# led-bike-suit-vest.net
KiCad netlist of a schematic drawn in EAGLE
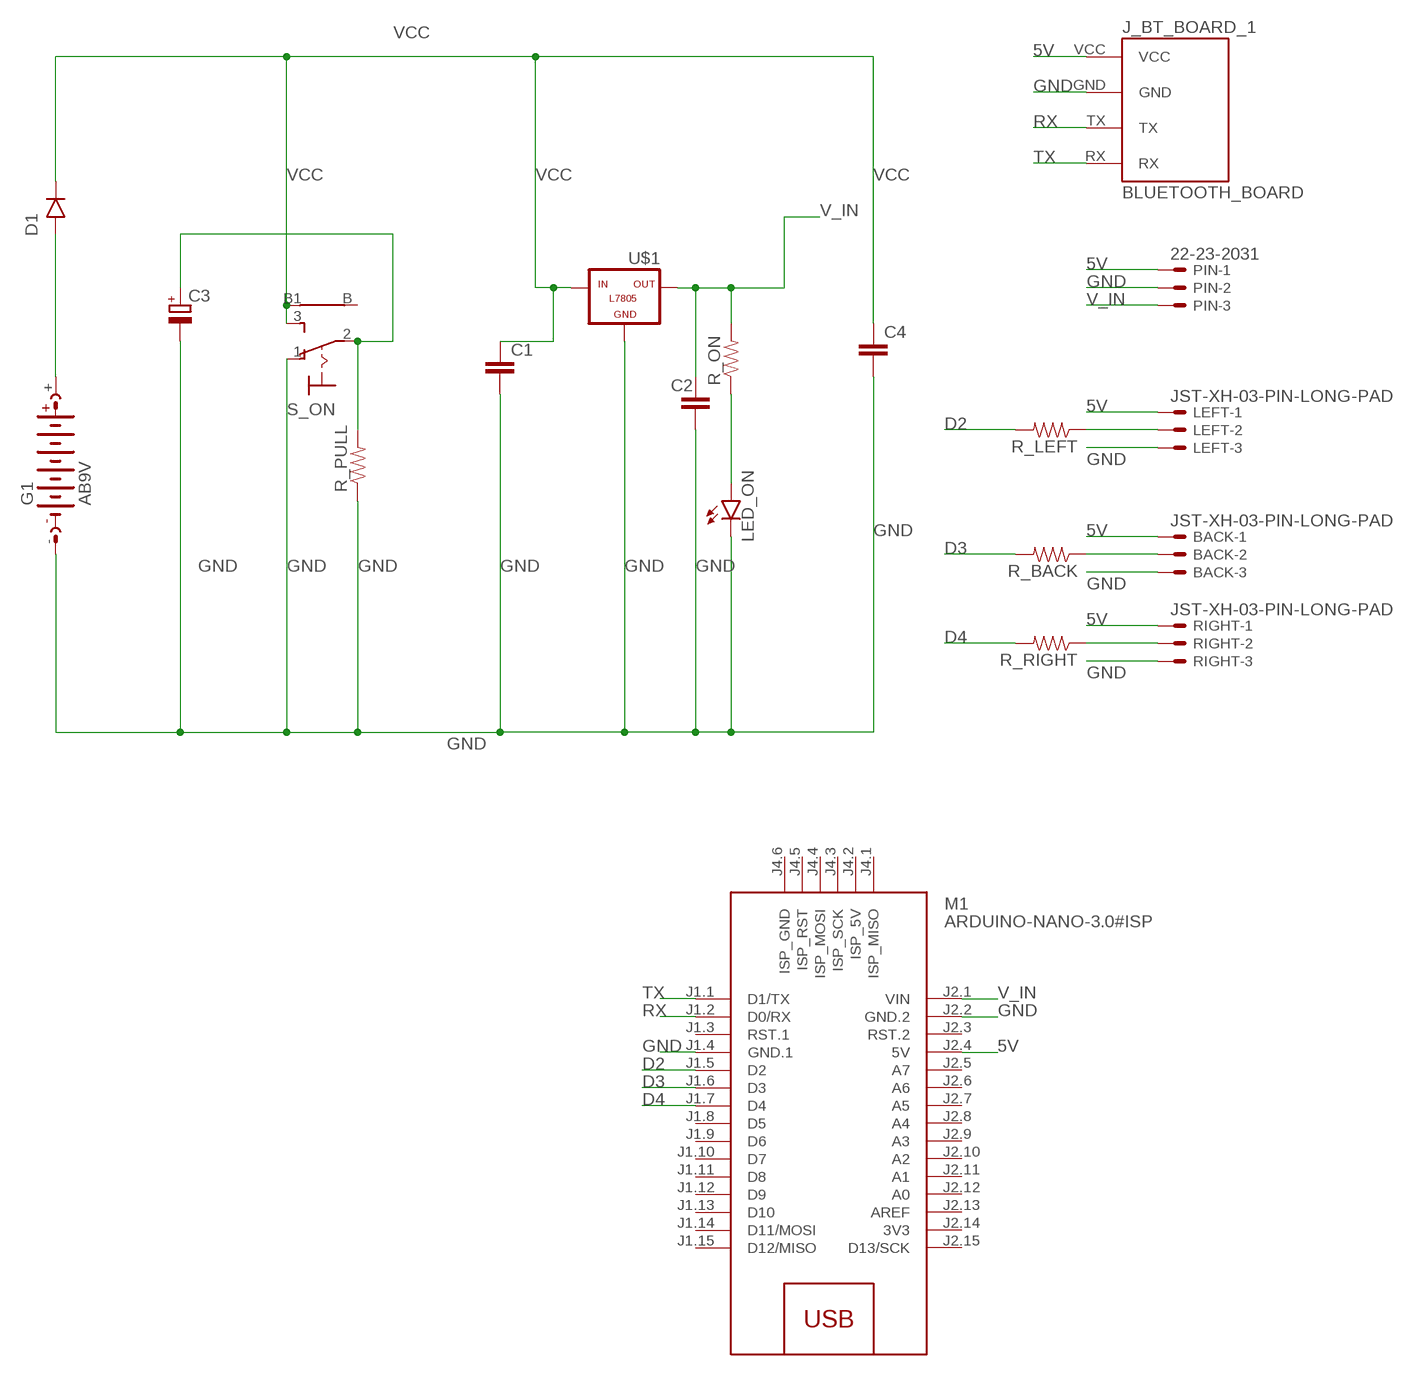
[diagram p0: schematic, sheet 1]

(export (version "E")
  (design (tool "Eeschema 10.0.6"))
  (components
    (comp (ref "BACK")
      (value "JST-XH-03-PIN-LONG-PAD")
      (footprint "eagle-import:JST-XH-03-PACKAGE-LONG-PAD")
      (libsource (lib "eagle-import") (part "JST-XH-03-PIN-LONG-PAD"))
    )
    (comp (ref "C1")
      (value "C2.5/4")
      (footprint "eagle-import:C2.5-4")
      (libsource (lib "eagle-import") (part "C2.5/4"))
    )
    (comp (ref "C2")
      (value "C2.5/4")
      (footprint "eagle-import:C2.5-4")
      (libsource (lib "eagle-import") (part "C2.5/4"))
    )
    (comp (ref "C3")
      (value "RCL_CPOL-EUE3.5-8")
      (footprint "eagle-import:ELECTROLYTIC_CAP_RCL_E3,5-8")
      (libsource (lib "eagle-import") (part "RCL_CPOL-EUE3.5-8"))
    )
    (comp (ref "C4")
      (value "C2.5/4")
      (footprint "eagle-import:C2.5-4")
      (libsource (lib "eagle-import") (part "C2.5/4"))
    )
    (comp (ref "D1")
      (value "1N4001")
      (footprint "eagle-import:DO41-10")
      (libsource (lib "eagle-import") (part "1N4001"))
    )
    (comp (ref "G1")
      (value "AB9V")
      (footprint "eagle-import:AB9V")
      (libsource (lib "eagle-import") (part "AB9V"))
    )
    (comp (ref "J_BT_BOARD_1")
      (value "BLUETOOTH_BOARD")
      (footprint "eagle-import:BT_BOARD_FOOTPRINT")
      (libsource (lib "eagle-import") (part "BLUETOOTH_BOARD"))
    )
    (comp (ref "LED_ON")
      (value "LED5MM")
      (footprint "eagle-import:LED5MM")
      (libsource (lib "eagle-import") (part "LED5MM"))
    )
    (comp (ref "LEFT")
      (value "JST-XH-03-PIN-LONG-PAD")
      (footprint "eagle-import:JST-XH-03-PACKAGE-LONG-PAD")
      (libsource (lib "eagle-import") (part "JST-XH-03-PIN-LONG-PAD"))
    )
    (comp (ref "M1")
      (value "ARDUINO-NANO-3.0#ISP")
      (footprint "eagle-import:ARDUINO-NANO-3.0#ISP")
      (libsource (lib "eagle-import") (part "ARDUINO-NANO-3.0#ISP"))
    )
    (comp (ref "PIN")
      (value "22-23-2031")
      (footprint "eagle-import:22-23-2031")
      (fields (field (name "MF") "MOLEX"))
      (libsource (lib "eagle-import") (part "22-23-2031"))
    )
    (comp (ref "RIGHT")
      (value "JST-XH-03-PIN-LONG-PAD")
      (footprint "eagle-import:JST-XH-03-PACKAGE-LONG-PAD")
      (libsource (lib "eagle-import") (part "JST-XH-03-PIN-LONG-PAD"))
    )
    (comp (ref "R_BACK")
      (value "PASSIVES_RESISTORPTH-1/4W")
      (footprint "eagle-import:SPARKFUN-PASSIVES_AXIAL-0.4")
      (libsource (lib "eagle-import") (part "PASSIVES_RESISTORPTH-1/4W"))
    )
    (comp (ref "R_LEFT")
      (value "PASSIVES_RESISTORPTH-1/4W")
      (footprint "eagle-import:SPARKFUN-PASSIVES_AXIAL-0.4")
      (libsource (lib "eagle-import") (part "PASSIVES_RESISTORPTH-1/4W"))
    )
    (comp (ref "R_ON")
      (value "PASSIVES_RESISTORPTH-1/4W")
      (footprint "eagle-import:SPARKFUN-PASSIVES_AXIAL-0.4")
      (libsource (lib "eagle-import") (part "PASSIVES_RESISTORPTH-1/4W"))
    )
    (comp (ref "R_PULL")
      (value "PASSIVES_RESISTORPTH-1/4W")
      (footprint "eagle-import:SPARKFUN-PASSIVES_AXIAL-0.4")
      (libsource (lib "eagle-import") (part "PASSIVES_RESISTORPTH-1/4W"))
    )
    (comp (ref "R_RIGHT")
      (value "PASSIVES_RESISTORPTH-1/4W")
      (footprint "eagle-import:SPARKFUN-PASSIVES_AXIAL-0.4")
      (libsource (lib "eagle-import") (part "PASSIVES_RESISTORPTH-1/4W"))
    )
    (comp (ref "S_ON")
      (value "9070-1W")
      (footprint "eagle-import:9070-1W")
      (libsource (lib "eagle-import") (part "9070-1W"))
    )
    (comp (ref "U$1")
      (value "-L7805")
      (footprint "eagle-import:L7805")
      (libsource (lib "eagle-import") (part "-L7805"))
    )
  )
  (nets
    (net (code "1") (name "/3V3") (class "Default")
      (node (ref "M1") (pin "J2.14") (pinfunction "3V3_J2.14") (pintype "power_in"))
    )
    (net (code "2") (name "/5V") (class "Default")
      (node (ref "BACK") (pin "1") (pinfunction "S_1") (pintype "passive"))
      (node (ref "J_BT_BOARD_1") (pin "VCC") (pinfunction "VCC_VCC") (pintype "bidirectional"))
      (node (ref "LEFT") (pin "1") (pinfunction "S_1") (pintype "passive"))
      (node (ref "M1") (pin "J2.4") (pinfunction "5V_J2.4") (pintype "power_in"))
      (node (ref "PIN") (pin "1") (pinfunction "S_1") (pintype "passive"))
      (node (ref "RIGHT") (pin "1") (pinfunction "S_1") (pintype "passive"))
    )
    (net (code "3") (name "/D2") (class "Default")
      (node (ref "M1") (pin "J1.5") (pinfunction "D2_J1.5") (pintype "bidirectional"))
      (node (ref "R_LEFT") (pin "P$2") (pinfunction "2_P$2") (pintype "passive"))
    )
    (net (code "4") (name "/D3") (class "Default")
      (node (ref "M1") (pin "J1.6") (pinfunction "D3_J1.6") (pintype "bidirectional"))
      (node (ref "R_BACK") (pin "P$2") (pinfunction "2_P$2") (pintype "passive"))
    )
    (net (code "5") (name "/D4") (class "Default")
      (node (ref "M1") (pin "J1.7") (pinfunction "D4_J1.7") (pintype "bidirectional"))
      (node (ref "R_RIGHT") (pin "P$2") (pinfunction "2_P$2") (pintype "passive"))
    )
    (net (code "6") (name "/GND") (class "Default")
      (node (ref "BACK") (pin "3") (pinfunction "S_3") (pintype "passive"))
      (node (ref "C1") (pin "2") (pinfunction "2_2") (pintype "passive"))
      (node (ref "C2") (pin "2") (pinfunction "2_2") (pintype "passive"))
      (node (ref "C3") (pin "-") (pinfunction "-_-") (pintype "passive"))
      (node (ref "C4") (pin "2") (pinfunction "2_2") (pintype "passive"))
      (node (ref "G1") (pin "-") (pinfunction "-_-") (pintype "passive"))
      (node (ref "J_BT_BOARD_1") (pin "GND") (pinfunction "GND_GND") (pintype "bidirectional"))
      (node (ref "LED_ON") (pin "K") (pinfunction "CATHODE_K") (pintype "passive"))
      (node (ref "LEFT") (pin "3") (pinfunction "S_3") (pintype "passive"))
      (node (ref "M1") (pin "J1.4") (pinfunction "GND.1_J1.4") (pintype "power_in"))
      (node (ref "M1") (pin "J2.2") (pinfunction "GND.2_J2.2") (pintype "power_in"))
      (node (ref "PIN") (pin "2") (pinfunction "S_2") (pintype "passive"))
      (node (ref "RIGHT") (pin "3") (pinfunction "S_3") (pintype "passive"))
      (node (ref "R_PULL") (pin "P$1") (pinfunction "1_P$1") (pintype "passive"))
      (node (ref "S_ON") (pin "1") (pinfunction "O_1") (pintype "passive"))
      (node (ref "U$1") (pin "GND") (pinfunction "GND_GND") (pintype "input"))
    )
    (net (code "7") (name "/RX") (class "Default")
      (node (ref "J_BT_BOARD_1") (pin "TX") (pinfunction "TX_TX") (pintype "bidirectional"))
      (node (ref "M1") (pin "J1.2") (pinfunction "D0/RX_J1.2") (pintype "bidirectional"))
    )
    (net (code "8") (name "/TX") (class "Default")
      (node (ref "J_BT_BOARD_1") (pin "RX") (pinfunction "RX_RX") (pintype "bidirectional"))
      (node (ref "M1") (pin "J1.1") (pinfunction "D1/TX_J1.1") (pintype "bidirectional"))
    )
    (net (code "9") (name "/VCC") (class "Default")
      (node (ref "C1") (pin "1") (pinfunction "1_1") (pintype "passive"))
      (node (ref "C4") (pin "1") (pinfunction "1_1") (pintype "passive"))
      (node (ref "D1") (pin "C") (pinfunction "CATHODE_C") (pintype "passive"))
      (node (ref "S_ON") (pin "3") (pinfunction "S_3") (pintype "passive"))
      (node (ref "S_ON") (pin "B1") (pinfunction "B1_B1") (pintype "passive"))
      (node (ref "U$1") (pin "IN") (pinfunction "IN_IN") (pintype "input"))
    )
    (net (code "10") (name "/V_IN") (class "Default")
      (node (ref "C2") (pin "1") (pinfunction "1_1") (pintype "passive"))
      (node (ref "M1") (pin "J2.1") (pinfunction "VIN_J2.1") (pintype "power_in"))
      (node (ref "PIN") (pin "3") (pinfunction "S_3") (pintype "passive"))
      (node (ref "R_ON") (pin "P$2") (pinfunction "2_P$2") (pintype "passive"))
      (node (ref "U$1") (pin "OUT") (pinfunction "OUT_OUT") (pintype "passive"))
    )
    (net (code "11") (name "Net-(BACKB-S)") (class "Default")
      (node (ref "BACK") (pin "2") (pinfunction "S_2") (pintype "passive"))
      (node (ref "R_BACK") (pin "P$1") (pinfunction "1_P$1") (pintype "passive"))
    )
    (net (code "12") (name "Net-(D1-ANODE)") (class "Default")
      (node (ref "D1") (pin "A") (pinfunction "ANODE_A") (pintype "passive"))
      (node (ref "G1") (pin "+") (pinfunction "+_+") (pintype "passive"))
    )
    (net (code "13") (name "Net-(LED_ON-ANODE)") (class "Default")
      (node (ref "LED_ON") (pin "A") (pinfunction "ANODE_A") (pintype "passive"))
      (node (ref "R_ON") (pin "P$1") (pinfunction "1_P$1") (pintype "passive"))
    )
    (net (code "14") (name "Net-(LEFTB-S)") (class "Default")
      (node (ref "LEFT") (pin "2") (pinfunction "S_2") (pintype "passive"))
      (node (ref "R_LEFT") (pin "P$1") (pinfunction "1_P$1") (pintype "passive"))
    )
    (net (code "15") (name "Net-(RIGHTB-S)") (class "Default")
      (node (ref "RIGHT") (pin "2") (pinfunction "S_2") (pintype "passive"))
      (node (ref "R_RIGHT") (pin "P$1") (pinfunction "1_P$1") (pintype "passive"))
    )
    (net (code "16") (name "Net-(R_PULL-2)") (class "Default")
      (node (ref "C3") (pin "+") (pinfunction "+_+") (pintype "passive"))
      (node (ref "R_PULL") (pin "P$2") (pinfunction "2_P$2") (pintype "passive"))
      (node (ref "S_ON") (pin "2") (pinfunction "P_2") (pintype "passive"))
    )
    (net (code "17") (name "unconnected-(M1-A0-PadJ2.12)") (class "Default")
      (node (ref "M1") (pin "J2.12") (pinfunction "A0_J2.12") (pintype "bidirectional"))
    )
    (net (code "18") (name "unconnected-(M1-A1-PadJ2.11)") (class "Default")
      (node (ref "M1") (pin "J2.11") (pinfunction "A1_J2.11") (pintype "bidirectional"))
    )
    (net (code "19") (name "unconnected-(M1-A2-PadJ2.10)") (class "Default")
      (node (ref "M1") (pin "J2.10") (pinfunction "A2_J2.10") (pintype "bidirectional"))
    )
    (net (code "20") (name "unconnected-(M1-A3-PadJ2.9)") (class "Default")
      (node (ref "M1") (pin "J2.9") (pinfunction "A3_J2.9") (pintype "bidirectional"))
    )
    (net (code "21") (name "unconnected-(M1-A4-PadJ2.8)") (class "Default")
      (node (ref "M1") (pin "J2.8") (pinfunction "A4_J2.8") (pintype "bidirectional"))
    )
    (net (code "22") (name "unconnected-(M1-A5-PadJ2.7)") (class "Default")
      (node (ref "M1") (pin "J2.7") (pinfunction "A5_J2.7") (pintype "bidirectional"))
    )
    (net (code "23") (name "unconnected-(M1-A6-PadJ2.6)") (class "Default")
      (node (ref "M1") (pin "J2.6") (pinfunction "A6_J2.6") (pintype "bidirectional"))
    )
    (net (code "24") (name "unconnected-(M1-A7-PadJ2.5)") (class "Default")
      (node (ref "M1") (pin "J2.5") (pinfunction "A7_J2.5") (pintype "bidirectional"))
    )
    (net (code "25") (name "unconnected-(M1-AREF-PadJ2.13)") (class "Default")
      (node (ref "M1") (pin "J2.13") (pinfunction "AREF_J2.13") (pintype "bidirectional"))
    )
    (net (code "26") (name "unconnected-(M1-D5-PadJ1.8)") (class "Default")
      (node (ref "M1") (pin "J1.8") (pinfunction "D5_J1.8") (pintype "bidirectional"))
    )
    (net (code "27") (name "unconnected-(M1-D6-PadJ1.9)") (class "Default")
      (node (ref "M1") (pin "J1.9") (pinfunction "D6_J1.9") (pintype "bidirectional"))
    )
    (net (code "28") (name "unconnected-(M1-D7-PadJ1.10)") (class "Default")
      (node (ref "M1") (pin "J1.10") (pinfunction "D7_J1.10") (pintype "bidirectional"))
    )
    (net (code "29") (name "unconnected-(M1-D8-PadJ1.11)") (class "Default")
      (node (ref "M1") (pin "J1.11") (pinfunction "D8_J1.11") (pintype "bidirectional"))
    )
    (net (code "30") (name "unconnected-(M1-D9-PadJ1.12)") (class "Default")
      (node (ref "M1") (pin "J1.12") (pinfunction "D9_J1.12") (pintype "bidirectional"))
    )
    (net (code "31") (name "unconnected-(M1-D10-PadJ1.13)") (class "Default")
      (node (ref "M1") (pin "J1.13") (pinfunction "D10_J1.13") (pintype "bidirectional"))
    )
    (net (code "32") (name "unconnected-(M1-D11{slash}MOSI-PadJ1.14)") (class "Default")
      (node (ref "M1") (pin "J1.14") (pinfunction "D11/MOSI_J1.14") (pintype "bidirectional"))
    )
    (net (code "33") (name "unconnected-(M1-D12{slash}MISO-PadJ1.15)") (class "Default")
      (node (ref "M1") (pin "J1.15") (pinfunction "D12/MISO_J1.15") (pintype "bidirectional"))
    )
    (net (code "34") (name "unconnected-(M1-D13{slash}SCK-PadJ2.15)") (class "Default")
      (node (ref "M1") (pin "J2.15") (pinfunction "D13/SCK_J2.15") (pintype "bidirectional"))
    )
    (net (code "35") (name "unconnected-(M1-ISP_5V-PadJ4.2)") (class "Default")
      (node (ref "M1") (pin "J4.2") (pinfunction "ISP_5V_J4.2") (pintype "bidirectional"))
    )
    (net (code "36") (name "unconnected-(M1-ISP_GND-PadJ4.6)") (class "Default")
      (node (ref "M1") (pin "J4.6") (pinfunction "ISP_GND_J4.6") (pintype "bidirectional"))
    )
    (net (code "37") (name "unconnected-(M1-ISP_MISO-PadJ4.1)") (class "Default")
      (node (ref "M1") (pin "J4.1") (pinfunction "ISP_MISO_J4.1") (pintype "bidirectional"))
    )
    (net (code "38") (name "unconnected-(M1-ISP_MOSI-PadJ4.4)") (class "Default")
      (node (ref "M1") (pin "J4.4") (pinfunction "ISP_MOSI_J4.4") (pintype "bidirectional"))
    )
    (net (code "39") (name "unconnected-(M1-ISP_RST-PadJ4.5)") (class "Default")
      (node (ref "M1") (pin "J4.5") (pinfunction "ISP_RST_J4.5") (pintype "bidirectional"))
    )
    (net (code "40") (name "unconnected-(M1-ISP_SCK-PadJ4.3)") (class "Default")
      (node (ref "M1") (pin "J4.3") (pinfunction "ISP_SCK_J4.3") (pintype "bidirectional"))
    )
    (net (code "41") (name "unconnected-(M1-RST.1-PadJ1.3)") (class "Default")
      (node (ref "M1") (pin "J1.3") (pinfunction "RST.1_J1.3") (pintype "bidirectional"))
    )
    (net (code "42") (name "unconnected-(M1-RST.2-PadJ2.3)") (class "Default")
      (node (ref "M1") (pin "J2.3") (pinfunction "RST.2_J2.3") (pintype "bidirectional"))
    )
    (net (code "43") (name "unconnected-(S_ON-PadB)") (class "Default")
      (node (ref "S_ON") (pin "B") (pinfunction "B_B") (pintype "passive"))
    )
  )
)
